# Boost_Convertor_V2_Schematic.net
KiCad netlist of a schematic drawn in Altium Designer
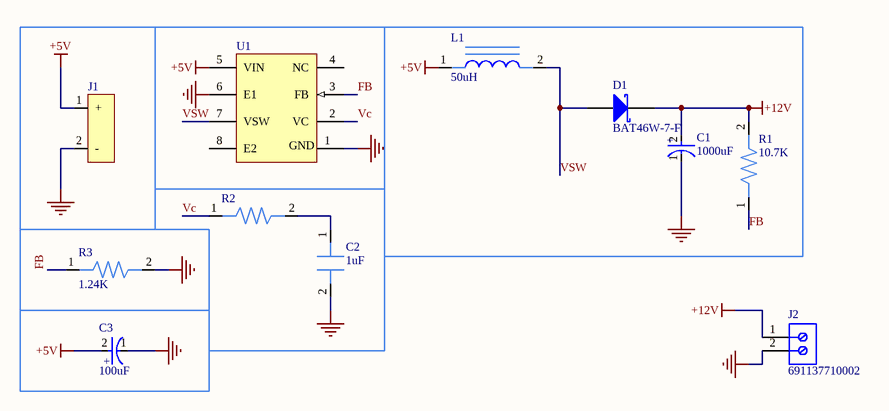
[diagram p0: Boost Convertor V2 Schematic.SchDoc]

(export (version "E")
  (design (tool "Eeschema 10.0.6"))
  (components
    (comp (ref "C1")
      (value "1000uF")
      (footprint "25PX1000MEFCT810X16")
      (fields
        (field (name "MANUFACTURER") "Rubycon")
        (field (name "MANUFACTURER PART NUMBER") "16ZLH1000MEFC10X16")
      )
      (libsource (lib "Boost") (part "16ZLH1000MEFC10X16"))
    )
    (comp (ref "C2")
      (value "1uF")
      (footprint "C1210C105K5RACTU")
      (description "Ceramic Capacitor 1uF")
      (fields
        (field (name "MANUFACTURER") "KEMET")
        (field (name "MANUFACTURER PART NUMBER") "ESL105M100AC3AA")
      )
      (libsource (lib "Boost") (part "CL10B105KA8NNNC"))
    )
    (comp (ref "C3")
      (value "100uF")
      (footprint "35ZLH100MEFC6.3X11")
      (description "CAP ALUM 100UF 20% 35V RADIAL")
      (fields (field (name "VOLTAGE") "35V") (field (name "TOLERANCE") "20%"))
      (libsource (lib "Boost") (part "a00bbbee19879c290e62620ae7e47b1"))
    )
    (comp (ref "D1")
      (value "BAT46W-7-F")
      (footprint "DIOD-SOD-123-2_V")
      (description "Surface Mount Schottky Barrier Diode, 100 V, -55 to 125 degC, 2-Pin SOD123, RoHS, Tape and Reel")
      (fields (field (name "MANUFACTURER") "Diodes Inc"))
      (libsource (lib "Altium Content Vault") (part "DIOD-DSKY-A1K2-2"))
    )
    (comp (ref "J1") (value "0022013037") (libsource (lib "Boost") (part "Molex Connector")))
    (comp (ref "J2")
      (value "691137710002")
      (footprint "691137710002")
      (libsource (lib "Altium Content Vault") (part "TBL - 1R - 02P - Screw"))
    )
    (comp (ref "L1")
      (value "50uH")
      (footprint "CTX50-1-52-R")
      (description "General Purpose Inductor, 50uH, 1 Element, Iron-Core")
      (fields
        (field (name "MANUFACTURER") "Eaton Cooper")
        (field (name "MANUFACTURER PART NUMBER") "CTX50-1-52-R")
      )
      (libsource (lib "Boost") (part "CTX50-1-52-R"))
    )
    (comp (ref "R1")
      (value "10.7K")
      (footprint "RC0805FR-0710K7L")
      (description "Fixed Resistor, Metal Film, 0.25W, 10700ohm, 250V, 1% +/-Tol, -100,100ppm/Cel")
      (fields
        (field (name "MANUFACTURER") "Yageo")
        (field (name "MANUFACTURER PART NUMBER") "MFR-25FBF52-10K7")
      )
      (libsource (lib "Boost") (part "RC0805FR-0710K7L"))
    )
    (comp (ref "R2")
      (value "~")
      (footprint "RC0805FR-071KL")
      (description "Fixed Resistor, Carbon Film, 0.25W, 1000ohm, 350V, 5% +/-Tol, -400,0ppm/Cel, Through Hole Mount")
      (fields
        (field (name "MANUFACTURER") "Stackpole Electronics")
        (field (name "MANUFACTURER PART NUMBER") "CF14JT1K00")
      )
      (libsource (lib "Boost") (part "RC0805FR-071KL"))
    )
    (comp (ref "R3")
      (value "1.24K")
      (footprint "RC0805FR-071K24L")
      (description "Fixed Resistor, Metal Film, 0.25W, 1240ohm, 250V, 1% +/-Tol, -100,100ppm/Cel")
      (fields
        (field (name "MANUFACTURER") "Yageo")
        (field (name "MANUFACTURER PART NUMBER") "MFR-25FBF52-1K24")
      )
      (libsource (lib "Boost") (part "RC0805FR-071K24L"))
    )
    (comp (ref "U1")
      (value "LT1172CN8#PBF")
      (footprint "LT1172CN8#PBF-ND")
      (description "100 kHz, 1.25 A, High Efficiency Switching Regulator, 8-pin DIP (N8-8), 0 to 100 degC, Pb-Free")
      (fields (field (name "MANUFACTURER") "Linear Technology"))
      (libsource (lib "Boost") (part "LT-LT1172-X8-8"))
    )
  )
  (nets
    (net (code "1") (name "+5V") (class "Default")
      (node (ref "C3") (pin "2") (pinfunction "A_2") (pintype "passive"))
      (node (ref "J1") (pin "1") (pinfunction "+_1") (pintype "passive"))
      (node (ref "L1") (pin "1") (pinfunction "1_1") (pintype "passive"))
      (node (ref "U1") (pin "5") (pinfunction "VIN_5") (pintype "power_in"))
    )
    (net (code "2") (name "+12V") (class "Default")
      (node (ref "C1") (pin "2") (pinfunction "A_2") (pintype "passive"))
      (node (ref "D1") (pin "2") (pinfunction "K_2") (pintype "passive"))
      (node (ref "J2") (pin "1") (pinfunction "1_1") (pintype "passive"))
      (node (ref "R1") (pin "2") (pinfunction "2_2") (pintype "passive"))
    )
    (net (code "3") (name "/FB") (class "Default")
      (node (ref "R1") (pin "1") (pinfunction "1_1") (pintype "passive"))
      (node (ref "R3") (pin "1") (pinfunction "1_1") (pintype "passive"))
      (node (ref "U1") (pin "3") (pinfunction "FB_3") (pintype "input"))
    )
    (net (code "4") (name "/VSW") (class "Default")
      (node (ref "D1") (pin "1") (pinfunction "A_1") (pintype "passive"))
      (node (ref "L1") (pin "2") (pinfunction "2_2") (pintype "passive"))
      (node (ref "U1") (pin "7") (pinfunction "VSW_7") (pintype "power_in"))
    )
    (net (code "5") (name "/Vc") (class "Default")
      (node (ref "R2") (pin "1") (pinfunction "1_1") (pintype "passive"))
      (node (ref "U1") (pin "2") (pinfunction "VC_2") (pintype "passive"))
    )
    (net (code "6") (name "GND") (class "Default")
      (node (ref "C1") (pin "1") (pinfunction "C_1") (pintype "passive"))
      (node (ref "C2") (pin "2") (pinfunction "2_2") (pintype "passive"))
      (node (ref "C3") (pin "1") (pinfunction "C_1") (pintype "passive"))
      (node (ref "J1") (pin "2") (pinfunction "-_2") (pintype "passive"))
      (node (ref "J2") (pin "2") (pinfunction "2_2") (pintype "passive"))
      (node (ref "R3") (pin "2") (pinfunction "2_2") (pintype "passive"))
      (node (ref "U1") (pin "6") (pinfunction "E1_6") (pintype "passive"))
    )
    (net (code "7") (name "Net-(C2-Pad1)") (class "Default")
      (node (ref "C2") (pin "1") (pinfunction "1_1") (pintype "passive"))
      (node (ref "R2") (pin "2") (pinfunction "2_2") (pintype "passive"))
    )
    (net (code "8") (name "unconnected-(U1-E2-Pad8)") (class "Default")
      (node (ref "U1") (pin "8") (pinfunction "E2_8") (pintype "passive"))
    )
    (net (code "9") (name "unconnected-(U1-GND-Pad1)") (class "Default")
      (node (ref "U1") (pin "1") (pinfunction "GND_1") (pintype "power_in"))
    )
    (net (code "10") (name "unconnected-(U1-NC-Pad4)") (class "Default")
      (node (ref "U1") (pin "4") (pinfunction "NC_4") (pintype "passive"))
    )
  )
)
